# Sheet1.net
KiCad netlist of a schematic drawn in Altium Designer
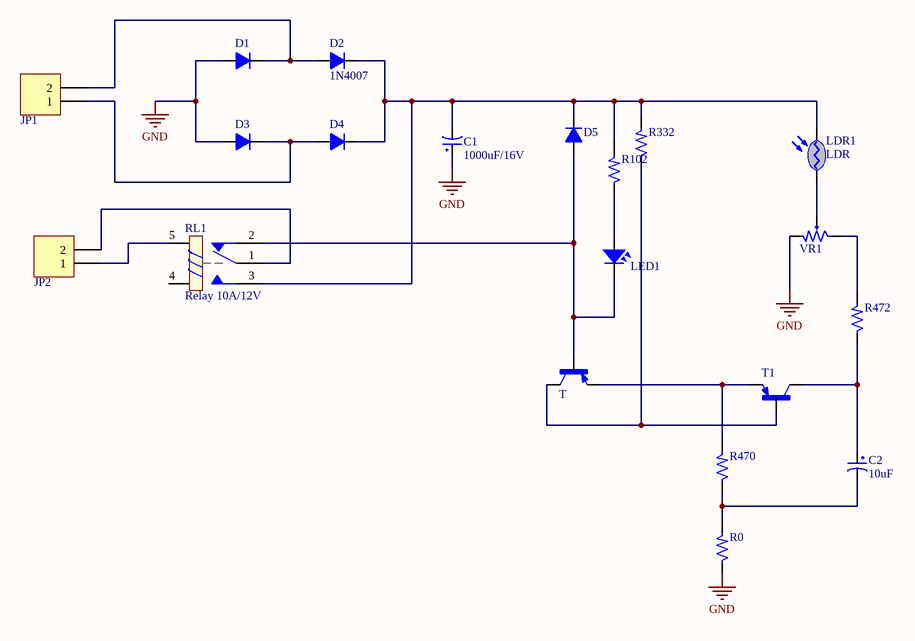
[diagram p0: Sheet1.SchDoc]

(export (version "E")
  (design (tool "Eeschema 10.0.6"))
  (components
    (comp (ref "C1")
      (value "1000uF/16V")
      (footprint "CP1.5/3.4")
      (description "Cap 1000uF/16V - 220uF/50V")
      (libsource (lib "syhaunguyen") (part "CP4"))
    )
    (comp (ref "C2")
      (value "10uF")
      (footprint "CP1/2")
      (description "Cap P  0,1uF < 22uF , 16 - 50V")
      (libsource (lib "syhaunguyen") (part "CP1"))
    )
    (comp (ref "D1")
      (value "1N4007")
      (footprint "D1A")
      (description "Diode 1A")
      (libsource (lib "syhaunguyen") (part "D1A"))
    )
    (comp (ref "D2")
      (value "1N4007")
      (footprint "D1A")
      (description "Diode 1A")
      (libsource (lib "syhaunguyen") (part "D1A"))
    )
    (comp (ref "D3")
      (value "1N4007")
      (footprint "D1A")
      (description "Diode 1A")
      (libsource (lib "syhaunguyen") (part "D1A"))
    )
    (comp (ref "D4")
      (value "1N4007")
      (footprint "D1A")
      (description "Diode 1A")
      (libsource (lib "syhaunguyen") (part "D1A"))
    )
    (comp (ref "D5")
      (value "1N4007")
      (footprint "D1A")
      (description "Diode 1A")
      (libsource (lib "syhaunguyen") (part "D1A"))
    )
    (comp (ref "JP1")
      (value "Header 2_1")
      (footprint "HED2")
      (description "Header, 2-Pin")
      (fields (field (name "MANUFACTURER") "Generic Components"))
      (libsource (lib "syhaunguyen") (part "Header 2_1"))
    )
    (comp (ref "JP2")
      (value "Header 2_1")
      (footprint "HED2")
      (description "Header, 2-Pin")
      (fields (field (name "MANUFACTURER") "Generic Components"))
      (libsource (lib "syhaunguyen") (part "Header 2_1"))
    )
    (comp (ref "LDR1")
      (value "LDR")
      (footprint "CDS")
      (description "Quang Tro")
      (libsource (lib "syhaunguyen") (part "LDR"))
    )
    (comp (ref "LED1")
      (value "LED")
      (footprint "LED-3")
      (description "LED Single colour Green and Red")
      (libsource (lib "syhaunguyen") (part "LED"))
    )
    (comp (ref "R0")
      (value "1k")
      (footprint "SM-RES-1206")
      (description "Resistor 1/4W")
      (libsource (lib "syhaunguyen") (part "R"))
    )
    (comp (ref "R102")
      (value "1k")
      (footprint "SM-RES-1206")
      (description "Resistor 1/4W")
      (libsource (lib "syhaunguyen") (part "R"))
    )
    (comp (ref "R332")
      (value "1k")
      (footprint "SM-RES-1206")
      (description "Resistor 1/4W")
      (libsource (lib "syhaunguyen") (part "R"))
    )
    (comp (ref "R470")
      (value "1k")
      (footprint "SM-RES-1206")
      (description "Resistor 1/4W")
      (libsource (lib "syhaunguyen") (part "R"))
    )
    (comp (ref "R472")
      (value "1k")
      (footprint "SM-RES-1206")
      (description "Resistor 1/4W")
      (libsource (lib "syhaunguyen") (part "R"))
    )
    (comp (ref "RL1")
      (value "Relay 10A/12V")
      (footprint "RL_SPDT_10A")
      (description "Relay SPDT,10A - 12VDC 5 Pin")
      (libsource (lib "syhaunguyen") (part "Relay 1"))
    )
    (comp (ref "T")
      (value "BC858C")
      (footprint "SOT23")
      (description "Bipolar _BJT_ Transistor PNP 30V 100mA 150MHz 310mW Surface Mount SOT-23-3")
      (fields (field (name "MF") "ON Semiconductor"))
      (libsource (lib "") (part "BC858C_1"))
    )
    (comp (ref "T1")
      (value "BC858C")
      (footprint "SOT23")
      (description "Bipolar _BJT_ Transistor PNP 30V 100mA 150MHz 310mW Surface Mount SOT-23-3")
      (fields (field (name "MF") "ON Semiconductor"))
      (libsource (lib "BC858C") (part "BC858C"))
    )
    (comp (ref "VR1")
      (value "10K")
      (footprint "VR")
      (description "Var Resistor")
      (libsource (lib "syhaunguyen") (part "VR1"))
    )
  )
  (nets
    (net (code "1") (name "GND") (class "Default")
      (node (ref "C1") (pin "1") (pinfunction "1_1") (pintype "passive"))
      (node (ref "D1") (pin "1") (pinfunction "A_1") (pintype "passive"))
      (node (ref "D3") (pin "1") (pinfunction "A_1") (pintype "passive"))
      (node (ref "R0") (pin "1") (pinfunction "1_1") (pintype "passive"))
      (node (ref "VR1") (pin "1") (pinfunction "1_1") (pintype "passive"))
    )
    (net (code "2") (name "Net-(C2-Pad2)") (class "Default")
      (node (ref "C2") (pin "2") (pinfunction "2_2") (pintype "passive"))
      (node (ref "R0") (pin "2") (pinfunction "2_2") (pintype "passive"))
      (node (ref "R470") (pin "1") (pinfunction "1_1") (pintype "passive"))
    )
    (net (code "3") (name "Net-(D1-K)") (class "Default")
      (node (ref "D1") (pin "2") (pinfunction "K_2") (pintype "passive"))
      (node (ref "D2") (pin "1") (pinfunction "A_1") (pintype "passive"))
      (node (ref "JP1") (pin "2") (pinfunction "2_2") (pintype "passive"))
    )
    (net (code "4") (name "Net-(D2-K)") (class "Default")
      (node (ref "C1") (pin "2") (pinfunction "2_2") (pintype "passive"))
      (node (ref "D2") (pin "2") (pinfunction "K_2") (pintype "passive"))
      (node (ref "D4") (pin "2") (pinfunction "K_2") (pintype "passive"))
      (node (ref "D5") (pin "2") (pinfunction "K_2") (pintype "passive"))
      (node (ref "LDR1") (pin "2") (pinfunction "K_2") (pintype "passive"))
      (node (ref "R102") (pin "2") (pinfunction "2_2") (pintype "passive"))
      (node (ref "R332") (pin "2") (pinfunction "2_2") (pintype "passive"))
      (node (ref "RL1") (pin "3") (pinfunction "3_3") (pintype "passive"))
    )
    (net (code "5") (name "Net-(D3-K)") (class "Default")
      (node (ref "D3") (pin "2") (pinfunction "K_2") (pintype "passive"))
      (node (ref "D4") (pin "1") (pinfunction "A_1") (pintype "passive"))
      (node (ref "JP1") (pin "1") (pinfunction "1_1") (pintype "passive"))
    )
    (net (code "6") (name "Net-(D5-A)") (class "Default")
      (node (ref "D5") (pin "1") (pinfunction "A_1") (pintype "passive"))
      (node (ref "LED1") (pin "2") (pinfunction "2_2") (pintype "passive"))
      (node (ref "RL1") (pin "2") (pinfunction "2_2") (pintype "passive"))
      (node (ref "T") (pin "1") (pinfunction "B_1") (pintype "passive"))
    )
    (net (code "7") (name "Net-(JP2-Pad1)") (class "Default")
      (node (ref "JP2") (pin "1") (pinfunction "1_1") (pintype "passive"))
      (node (ref "RL1") (pin "5") (pinfunction "5_5") (pintype "passive"))
    )
    (net (code "8") (name "Net-(JP2-Pad2)") (class "Default")
      (node (ref "JP2") (pin "2") (pinfunction "2_2") (pintype "passive"))
      (node (ref "RL1") (pin "1") (pinfunction "1_1") (pintype "passive"))
    )
    (net (code "9") (name "Net-(LDR1-A)") (class "Default")
      (node (ref "LDR1") (pin "1") (pinfunction "A_1") (pintype "passive"))
      (node (ref "VR1") (pin "2") (pinfunction "2_2") (pintype "passive"))
    )
    (net (code "10") (name "Net-(LED1-Pad1)") (class "Default")
      (node (ref "LED1") (pin "1") (pinfunction "1_1") (pintype "passive"))
      (node (ref "R102") (pin "1") (pinfunction "1_1") (pintype "passive"))
    )
    (net (code "11") (name "Net-(R472-Pad2)") (class "Default")
      (node (ref "R472") (pin "2") (pinfunction "2_2") (pintype "passive"))
      (node (ref "VR1") (pin "3") (pinfunction "3_3") (pintype "passive"))
    )
    (net (code "12") (name "Net-(T-C)") (class "Default")
      (node (ref "R332") (pin "1") (pinfunction "1_1") (pintype "passive"))
      (node (ref "T") (pin "3") (pinfunction "C_3") (pintype "passive"))
      (node (ref "T1") (pin "1") (pinfunction "B_1") (pintype "passive"))
    )
    (net (code "13") (name "Net-(T-E)") (class "Default")
      (node (ref "R470") (pin "2") (pinfunction "2_2") (pintype "passive"))
      (node (ref "T") (pin "2") (pinfunction "E_2") (pintype "passive"))
      (node (ref "T1") (pin "2") (pinfunction "E_2") (pintype "passive"))
    )
    (net (code "14") (name "Net-(T1-C)") (class "Default")
      (node (ref "C2") (pin "1") (pinfunction "1_1") (pintype "passive"))
      (node (ref "R472") (pin "1") (pinfunction "1_1") (pintype "passive"))
      (node (ref "T1") (pin "3") (pinfunction "C_3") (pintype "passive"))
    )
    (net (code "15") (name "unconnected-(RL1-Pad4)") (class "Default")
      (node (ref "RL1") (pin "4") (pinfunction "4_4") (pintype "passive"))
    )
  )
)
